# LiPo_Battery_Charger.net
KiCad netlist of a schematic drawn in Altium Designer
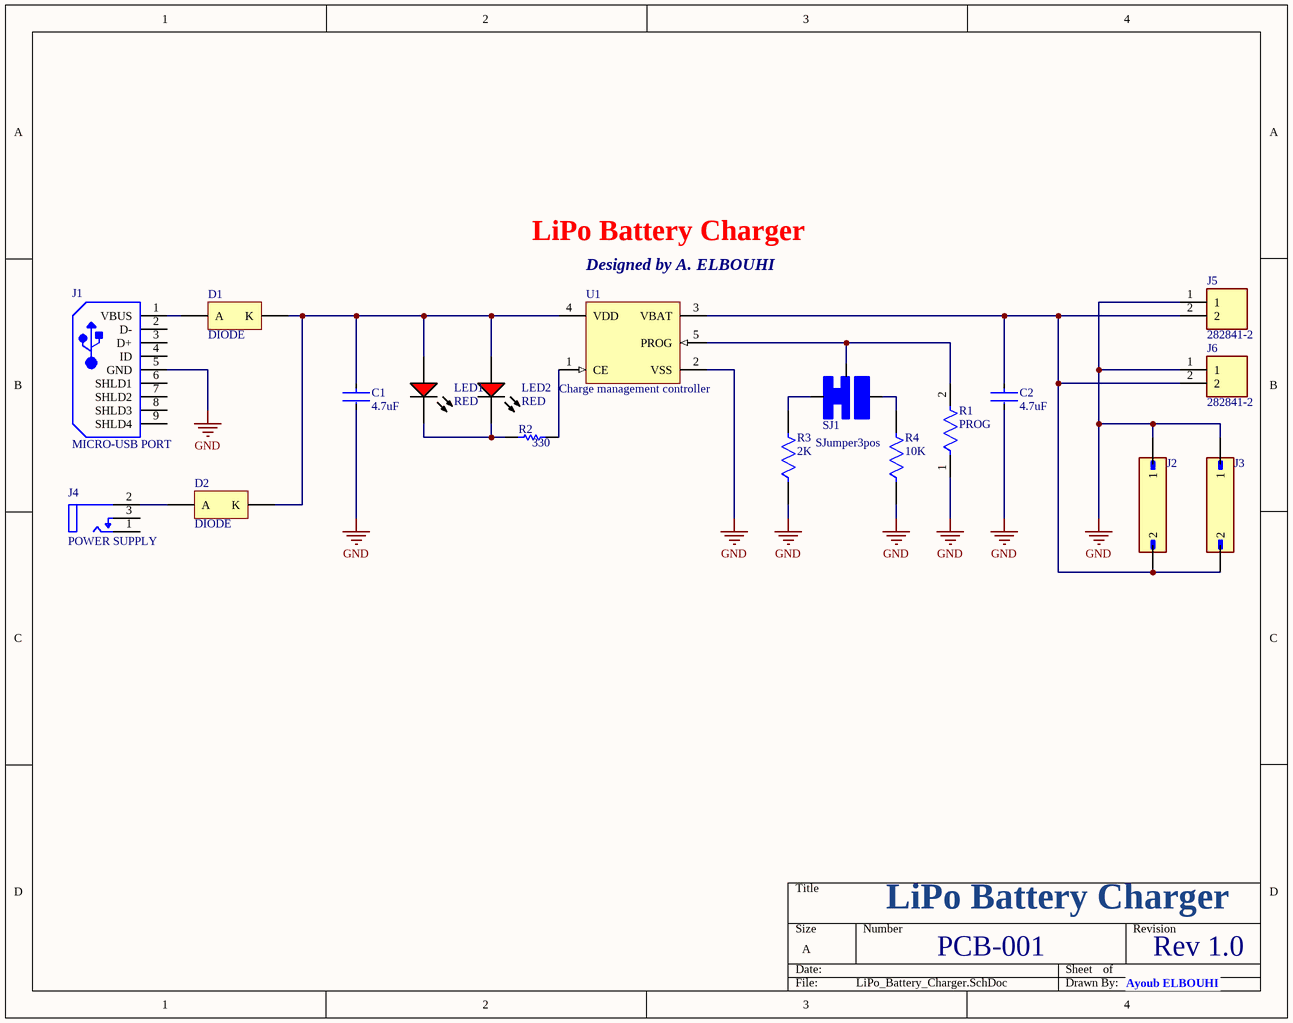
[diagram p0: LiPo_Battery_Charger.SchDoc]

(export (version "E")
  (design (tool "Eeschema 10.0.6"))
  (components
    (comp (ref "C1")
      (value "4.7uF")
      (footprint "FP-GRM155-0_15-IPC_C")
      (description "Chip Multilayer Ceramic Capacitors for General Purpose, 0402, 4.7uF, X6S, 22%, 20%, 6.3V")
      (fields (field (name "TOLERANCE") "20%"))
      (libsource (lib "Altium Content Vault") (part "b4654b650e69147ec39a6b967a45e02"))
    )
    (comp (ref "C2")
      (value "4.7uF")
      (footprint "FP-GRM155-0_15-IPC_C")
      (description "Chip Multilayer Ceramic Capacitors for General Purpose, 0402, 4.7uF, X6S, 22%, 20%, 6.3V")
      (fields (field (name "TOLERANCE") "20%"))
      (libsource (lib "Altium Content Vault") (part "b4654b650e69147ec39a6b967a45e02"))
    )
    (comp (ref "D1")
      (value "DIODE")
      (footprint "ONSC-SMA-2-403D-02_V")
      (description "Schottky Power Rectifier, 2-Pin SMA, Pb-Free, Tape and Reel")
      (fields (field (name "PARTNUMBER") "MBRA140T3G") (field (name "MANUFACTURER") "On Semiconductor"))
      (libsource (lib "Altium Content Vault") (part "ONSC-D-K1A2-2_A"))
    )
    (comp (ref "D2")
      (value "DIODE")
      (footprint "ONSC-SMA-2-403D-02_V")
      (description "Schottky Power Rectifier, 2-Pin SMA, Pb-Free, Tape and Reel")
      (fields (field (name "PARTNUMBER") "MBRA140T3G") (field (name "MANUFACTURER") "On Semiconductor"))
      (libsource (lib "Altium Content Vault") (part "ONSC-D-K1A2-2_A"))
    )
    (comp (ref "J1")
      (value "MICRO-USB PORT")
      (footprint "FCI-10104110-0001LF_V")
      (description "Micro USB, Receptacle, -55 to 85 degC, 5-Pin SMD, RoHS, Tape and Reel")
      (fields (field (name "MANUFACTURER") "FCI Electronics"))
      (libsource (lib "Altium Content Vault") (part "USB-5-4SHLD"))
    )
    (comp (ref "J2")
      (value "67997-402HLF")
      (footprint "AMPHENOL_67997-402HLF")
      (fields (field (name "MF") "{'manufacturer': u'Amphenol ICC (FCI)'}"))
      (libsource (lib "67997-402HLF") (part "67997-402HLF"))
    )
    (comp (ref "J3")
      (value "67997-402HLF")
      (footprint "AMPHENOL_67997-402HLF")
      (fields (field (name "MF") "{'manufacturer': u'Amphenol ICC (FCI)'}"))
      (libsource (lib "67997-402HLF") (part "67997-402HLF"))
    )
    (comp (ref "J4")
      (value "POWER SUPPLY")
      (footprint "FP-RASM722PTR13X-MFG")
      (description "CONN PWR JACK 2.1X5.5MM SOLDER")
      (libsource (lib "Altium Content Vault") (part "69023cd999ddc70d2a190894d9bbb58"))
    )
    (comp (ref "J5")
      (value "282841-2")
      (footprint "TE_282841-2")
      (description "Conn Terminal Block 2 POS 5.08mm Solder ST Thru-Hole 17.5A/Contact")
      (fields (field (name "MF") "TE Connectivity"))
      (libsource (lib "282841-2") (part "282841-2"))
    )
    (comp (ref "J6")
      (value "282841-2")
      (footprint "TE_282841-2")
      (description "Conn Terminal Block 2 POS 5.08mm Solder ST Thru-Hole 17.5A/Contact")
      (fields (field (name "MF") "TE Connectivity"))
      (libsource (lib "282841-2") (part "282841-2"))
    )
    (comp (ref "LED1")
      (value "RED")
      (footprint "INDPR60-254-520X380X650")
      (description "Radial LED, 12.6 mcd, 20 mA, 2 V, -55 to 100 degC, 2-Pin THD, RoHS, Bulk")
      (fields (field (name "TOLERANCE") "20%"))
      (libsource (lib "Altium Content Vault") (part "LED-RED-AK-2"))
    )
    (comp (ref "LED2")
      (value "RED")
      (footprint "INDPR60-254-520X380X650")
      (description "Radial LED, 12.6 mcd, 20 mA, 2 V, -55 to 100 degC, 2-Pin THD, RoHS, Bulk")
      (fields (field (name "TOLERANCE") "20%"))
      (libsource (lib "Altium Content Vault") (part "LED-RED-AK-2"))
    )
    (comp (ref "R1")
      (value "PROG")
      (footprint "FP-CF18-MFG")
      (description "RES 10K OHM 1/8W 5% CF AXIAL")
      (fields
        (field (name "MANUFACTURER PART NUMBER") "CF18JT10K0")
        (field (name "MANUFACTURER") "Stackpole Electronics")
      )
      (libsource (lib "") (part "1029c3af85768c4190bb7ad29bc67b5_1"))
    )
    (comp (ref "R2")
      (value "330")
      (footprint "RESC3225X60X45ML20T20")
      (fields (field (name "PART NUMBER") "CRCW1210330RJNTA") (field (name "MANUFACTURER") "Vishay Dale"))
      (libsource (lib "Altium Content Vault") (part "RES"))
    )
    (comp (ref "R3")
      (value "2K")
      (footprint "FP-CR0603-IPC_B")
      (description "Thick Film Chip Resistors 0603 2kΩ 0.1W 5% 200ppm/°C")
      (fields (field (name "TOLERANCE") "5%"))
      (libsource (lib "Altium Content Vault") (part "1029c3af85768c4190bb7ad29bc67b5"))
    )
    (comp (ref "R4")
      (value "10K")
      (footprint "FP-TFCR0805-IPC_B")
      (description "RES Thin Film,  10kΩ, 0.1%, 0.1W, 50ppm/°C, 0805")
      (libsource (lib "Altium Content Vault") (part "1029c3af85768c4190bb7ad29bc67b5"))
    )
    (comp (ref "SJ1")
      (value "SJumper3pos")
      (footprint "PCBComponent_1")
      (description "solder jumper 3 pins")
      (libsource (lib "solder_jumper_3posSchLib") (part "Solder_jumper_3pos"))
    )
    (comp (ref "U1")
      (value "Charge management controller")
      (footprint "SOT-23-OT5_M")
      (libsource (lib "Altium Content Vault") (part "PM-BM-MCP7381X-SOT5"))
    )
  )
  (nets
    (net (code "1") (name "GND") (class "Default")
      (node (ref "C1") (pin "2") (pinfunction "2_2") (pintype "passive"))
      (node (ref "C2") (pin "2") (pinfunction "2_2") (pintype "passive"))
      (node (ref "J1") (pin "5") (pinfunction "GND_5") (pintype "power_in"))
      (node (ref "J2") (pin "1") (pinfunction "1_1") (pintype "passive"))
      (node (ref "J3") (pin "1") (pinfunction "1_1") (pintype "passive"))
      (node (ref "J5") (pin "1") (pinfunction "1_1") (pintype "passive"))
      (node (ref "J6") (pin "1") (pinfunction "1_1") (pintype "passive"))
      (node (ref "R1") (pin "1") (pinfunction "1_1") (pintype "passive"))
      (node (ref "R3") (pin "1") (pinfunction "1_1") (pintype "passive"))
      (node (ref "R4") (pin "1") (pinfunction "1_1") (pintype "passive"))
      (node (ref "U1") (pin "2") (pinfunction "VSS_2") (pintype "power_in"))
    )
    (net (code "2") (name "Net-(D1-A)") (class "Default")
      (node (ref "D1") (pin "2") (pinfunction "A_2") (pintype "passive"))
      (node (ref "J1") (pin "1") (pinfunction "VBUS_1") (pintype "power_in"))
    )
    (net (code "3") (name "Net-(D1-K)") (class "Default")
      (node (ref "C1") (pin "1") (pinfunction "1_1") (pintype "passive"))
      (node (ref "D1") (pin "1") (pinfunction "K_1") (pintype "passive"))
      (node (ref "D2") (pin "1") (pinfunction "K_1") (pintype "passive"))
      (node (ref "LED1") (pin "1") (pinfunction "A_1") (pintype "passive"))
      (node (ref "LED2") (pin "1") (pinfunction "A_1") (pintype "passive"))
      (node (ref "U1") (pin "4") (pinfunction "VDD_4") (pintype "power_in"))
    )
    (net (code "4") (name "Net-(D2-A)") (class "Default")
      (node (ref "D2") (pin "2") (pinfunction "A_2") (pintype "passive"))
      (node (ref "J4") (pin "2") (pinfunction "SLEEVE_TERMINAL_2") (pintype "passive"))
    )
    (net (code "5") (name "Net-(LED1-K)") (class "Default")
      (node (ref "LED1") (pin "2") (pinfunction "K_2") (pintype "passive"))
      (node (ref "LED2") (pin "2") (pinfunction "K_2") (pintype "passive"))
      (node (ref "R2") (pin "1") (pinfunction "1_1") (pintype "passive"))
    )
    (net (code "6") (name "Net-(R3-Pad2)") (class "Default")
      (node (ref "R3") (pin "2") (pinfunction "2_2") (pintype "passive"))
      (node (ref "SJ1") (pin "1") (pinfunction "1_1") (pintype "passive"))
    )
    (net (code "7") (name "Net-(R4-Pad2)") (class "Default")
      (node (ref "R4") (pin "2") (pinfunction "2_2") (pintype "passive"))
      (node (ref "SJ1") (pin "3") (pinfunction "3_3") (pintype "passive"))
    )
    (net (code "8") (name "Net-(U1-CE)") (class "Default")
      (node (ref "R2") (pin "2") (pinfunction "2_2") (pintype "passive"))
      (node (ref "U1") (pin "1") (pinfunction "CE_1") (pintype "input"))
    )
    (net (code "9") (name "Net-(U1-PROG)") (class "Default")
      (node (ref "R1") (pin "2") (pinfunction "2_2") (pintype "passive"))
      (node (ref "SJ1") (pin "2") (pinfunction "2_2") (pintype "passive"))
      (node (ref "U1") (pin "5") (pinfunction "PROG_5") (pintype "input"))
    )
    (net (code "10") (name "Net-(U1-VBAT)") (class "Default")
      (node (ref "C2") (pin "1") (pinfunction "1_1") (pintype "passive"))
      (node (ref "J2") (pin "2") (pinfunction "2_2") (pintype "passive"))
      (node (ref "J3") (pin "2") (pinfunction "2_2") (pintype "passive"))
      (node (ref "J5") (pin "2") (pinfunction "2_2") (pintype "passive"))
      (node (ref "J6") (pin "2") (pinfunction "2_2") (pintype "passive"))
      (node (ref "U1") (pin "3") (pinfunction "VBAT_3") (pintype "power_in"))
    )
    (net (code "11") (name "unconnected-(J1-D+-Pad3)") (class "Default")
      (node (ref "J1") (pin "3") (pinfunction "D+_3") (pintype "passive"))
    )
    (net (code "12") (name "unconnected-(J1-D--Pad2)") (class "Default")
      (node (ref "J1") (pin "2") (pinfunction "D-_2") (pintype "passive"))
    )
    (net (code "13") (name "unconnected-(J1-ID-Pad4)") (class "Default")
      (node (ref "J1") (pin "4") (pinfunction "ID_4") (pintype "passive"))
    )
    (net (code "14") (name "unconnected-(J1-SHLD1-Pad6)") (class "Default")
      (node (ref "J1") (pin "6") (pinfunction "SHLD1_6") (pintype "passive"))
    )
    (net (code "15") (name "unconnected-(J1-SHLD2-Pad7)") (class "Default")
      (node (ref "J1") (pin "7") (pinfunction "SHLD2_7") (pintype "passive"))
    )
    (net (code "16") (name "unconnected-(J1-SHLD3-Pad8)") (class "Default")
      (node (ref "J1") (pin "8") (pinfunction "SHLD3_8") (pintype "passive"))
    )
    (net (code "17") (name "unconnected-(J1-SHLD4-Pad9)") (class "Default")
      (node (ref "J1") (pin "9") (pinfunction "SHLD4_9") (pintype "passive"))
    )
    (net (code "18") (name "unconnected-(J4-SHUNT_TERMINAL-Pad3)") (class "Default")
      (node (ref "J4") (pin "3") (pinfunction "SHUNT_TERMINAL_3") (pintype "passive"))
    )
    (net (code "19") (name "unconnected-(J4-TIP_TERMINAL(CENTER_PIN)-Pad1)") (class "Default")
      (node (ref "J4") (pin "1") (pinfunction "TIP_TERMINAL(CENTER_PIN)_1") (pintype "passive"))
    )
  )
)
